# mechanical.net
KiCad netlist of a schematic drawn in Altium Designer
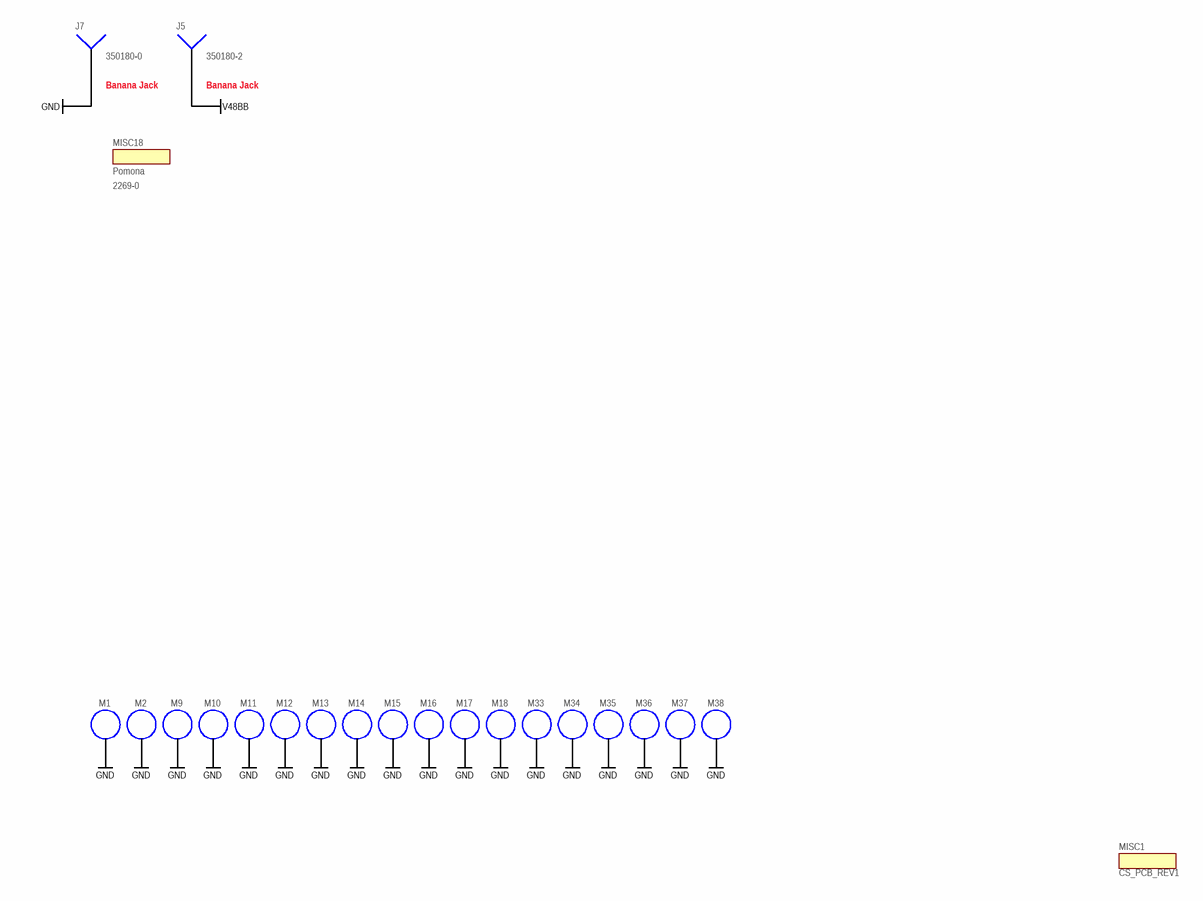
[diagram p0: mechanical.SchDoc]

(export (version "E")
  (design (tool "Eeschema 10.0.6"))
  (components
    (comp (ref "J5")
      (value "350180-2")
      (footprint "POWER_PAD")
      (description "Test Probe Assembly; Red")
      (fields (field (name "MANUFACTURER") "TE Connectivity"))
      (libsource (lib "Miscellaneous Connectors") (part "Socket"))
    )
    (comp (ref "J7")
      (value "350180-0")
      (footprint "POWER_PAD")
      (description "Test Probe Assembly; Black")
      (fields (field (name "MANUFACTURER") "TE Connectivity"))
      (libsource (lib "Miscellaneous Connectors") (part "Socket"))
    )
    (comp (ref "M1")
      (value "MOUNT")
      (footprint "MOUNTM3")
      (description "M3 Standard Fit Hole")
      (libsource (lib "copper_suicide") (part "MOUNT"))
    )
    (comp (ref "M2")
      (value "MOUNT")
      (footprint "MOUNTM3")
      (description "M3 Standard Fit Hole")
      (libsource (lib "copper_suicide") (part "MOUNT"))
    )
    (comp (ref "M9")
      (value "MOUNT")
      (footprint "MOUNTM3")
      (description "M3 Standard Fit Hole")
      (libsource (lib "copper_suicide") (part "MOUNT"))
    )
    (comp (ref "M10")
      (value "MOUNT")
      (footprint "MOUNTM3")
      (description "M3 Standard Fit Hole")
      (libsource (lib "copper_suicide") (part "MOUNT"))
    )
    (comp (ref "M11")
      (value "MOUNT")
      (footprint "MOUNTM3")
      (description "M3 Standard Fit Hole")
      (libsource (lib "copper_suicide") (part "MOUNT"))
    )
    (comp (ref "M12")
      (value "MOUNT")
      (footprint "MOUNTM3")
      (description "M3 Standard Fit Hole")
      (libsource (lib "copper_suicide") (part "MOUNT"))
    )
    (comp (ref "M13")
      (value "MOUNT")
      (footprint "MOUNTM3")
      (description "M3 Standard Fit Hole")
      (libsource (lib "copper_suicide") (part "MOUNT"))
    )
    (comp (ref "M14")
      (value "MOUNT")
      (footprint "MOUNTM3")
      (description "M3 Standard Fit Hole")
      (libsource (lib "copper_suicide") (part "MOUNT"))
    )
    (comp (ref "M15")
      (value "MOUNT")
      (footprint "MOUNTM3")
      (description "M3 Standard Fit Hole")
      (libsource (lib "copper_suicide") (part "MOUNT"))
    )
    (comp (ref "M16")
      (value "MOUNT")
      (footprint "MOUNTM3")
      (description "M3 Standard Fit Hole")
      (libsource (lib "copper_suicide") (part "MOUNT"))
    )
    (comp (ref "M17")
      (value "MOUNT")
      (footprint "MOUNTM3")
      (description "M3 Standard Fit Hole")
      (libsource (lib "copper_suicide") (part "MOUNT"))
    )
    (comp (ref "M18")
      (value "MOUNT")
      (footprint "MOUNTM3")
      (description "M3 Standard Fit Hole")
      (libsource (lib "copper_suicide") (part "MOUNT"))
    )
    (comp (ref "M33")
      (value "MOUNT")
      (footprint "MOUNTM3")
      (description "M3 Standard Fit Hole")
      (libsource (lib "copper_suicide") (part "MOUNT"))
    )
    (comp (ref "M34")
      (value "MOUNT")
      (footprint "MOUNTM3")
      (description "M3 Standard Fit Hole")
      (libsource (lib "copper_suicide") (part "MOUNT"))
    )
    (comp (ref "M35")
      (value "MOUNT")
      (footprint "MOUNTM3")
      (description "M3 Standard Fit Hole")
      (libsource (lib "copper_suicide") (part "MOUNT"))
    )
    (comp (ref "M36")
      (value "MOUNT")
      (footprint "MOUNTM3")
      (description "M3 Standard Fit Hole")
      (libsource (lib "copper_suicide") (part "MOUNT"))
    )
    (comp (ref "M37")
      (value "MOUNT")
      (footprint "MOUNTM3")
      (description "M3 Standard Fit Hole")
      (libsource (lib "copper_suicide") (part "MOUNT"))
    )
    (comp (ref "M38")
      (value "MOUNT")
      (footprint "MOUNTM3")
      (description "M3 Standard Fit Hole")
      (libsource (lib "copper_suicide") (part "MOUNT"))
    )
    (comp (ref "MISC1")
      (value "CS_PCB_REV1")
      (description "Copper Suicide PCB")
      (fields (field (name "MANUFACTURER") "Signal Laboratories, Inc."))
      (libsource (lib "harwin") (part "M50-1900005"))
    )
    (comp (ref "MISC18")
      (value "2269-0")
      (description "Double Banana Jack Connector")
      (fields (field (name "MANUFACTURER") "Pomona"))
      (libsource (lib "harwin") (part "M50-1900005"))
    )
  )
  (nets
    (net (code "1") (name "GND") (class "Default")
      (node (ref "J7") (pin "1") (pinfunction "1_1") (pintype "passive"))
      (node (ref "M1") (pin "1") (pinfunction "MNT_1") (pintype "passive"))
      (node (ref "M10") (pin "1") (pinfunction "MNT_1") (pintype "passive"))
      (node (ref "M11") (pin "1") (pinfunction "MNT_1") (pintype "passive"))
      (node (ref "M12") (pin "1") (pinfunction "MNT_1") (pintype "passive"))
      (node (ref "M13") (pin "1") (pinfunction "MNT_1") (pintype "passive"))
      (node (ref "M14") (pin "1") (pinfunction "MNT_1") (pintype "passive"))
      (node (ref "M15") (pin "1") (pinfunction "MNT_1") (pintype "passive"))
      (node (ref "M16") (pin "1") (pinfunction "MNT_1") (pintype "passive"))
      (node (ref "M17") (pin "1") (pinfunction "MNT_1") (pintype "passive"))
      (node (ref "M18") (pin "1") (pinfunction "MNT_1") (pintype "passive"))
      (node (ref "M2") (pin "1") (pinfunction "MNT_1") (pintype "passive"))
      (node (ref "M33") (pin "1") (pinfunction "MNT_1") (pintype "passive"))
      (node (ref "M34") (pin "1") (pinfunction "MNT_1") (pintype "passive"))
      (node (ref "M35") (pin "1") (pinfunction "MNT_1") (pintype "passive"))
      (node (ref "M36") (pin "1") (pinfunction "MNT_1") (pintype "passive"))
      (node (ref "M37") (pin "1") (pinfunction "MNT_1") (pintype "passive"))
      (node (ref "M38") (pin "1") (pinfunction "MNT_1") (pintype "passive"))
      (node (ref "M9") (pin "1") (pinfunction "MNT_1") (pintype "passive"))
    )
    (net (code "2") (name "V48BB") (class "Default")
      (node (ref "J5") (pin "1") (pinfunction "1_1") (pintype "passive"))
    )
  )
)
